# motor.net
KiCad netlist of a schematic drawn in EAGLE
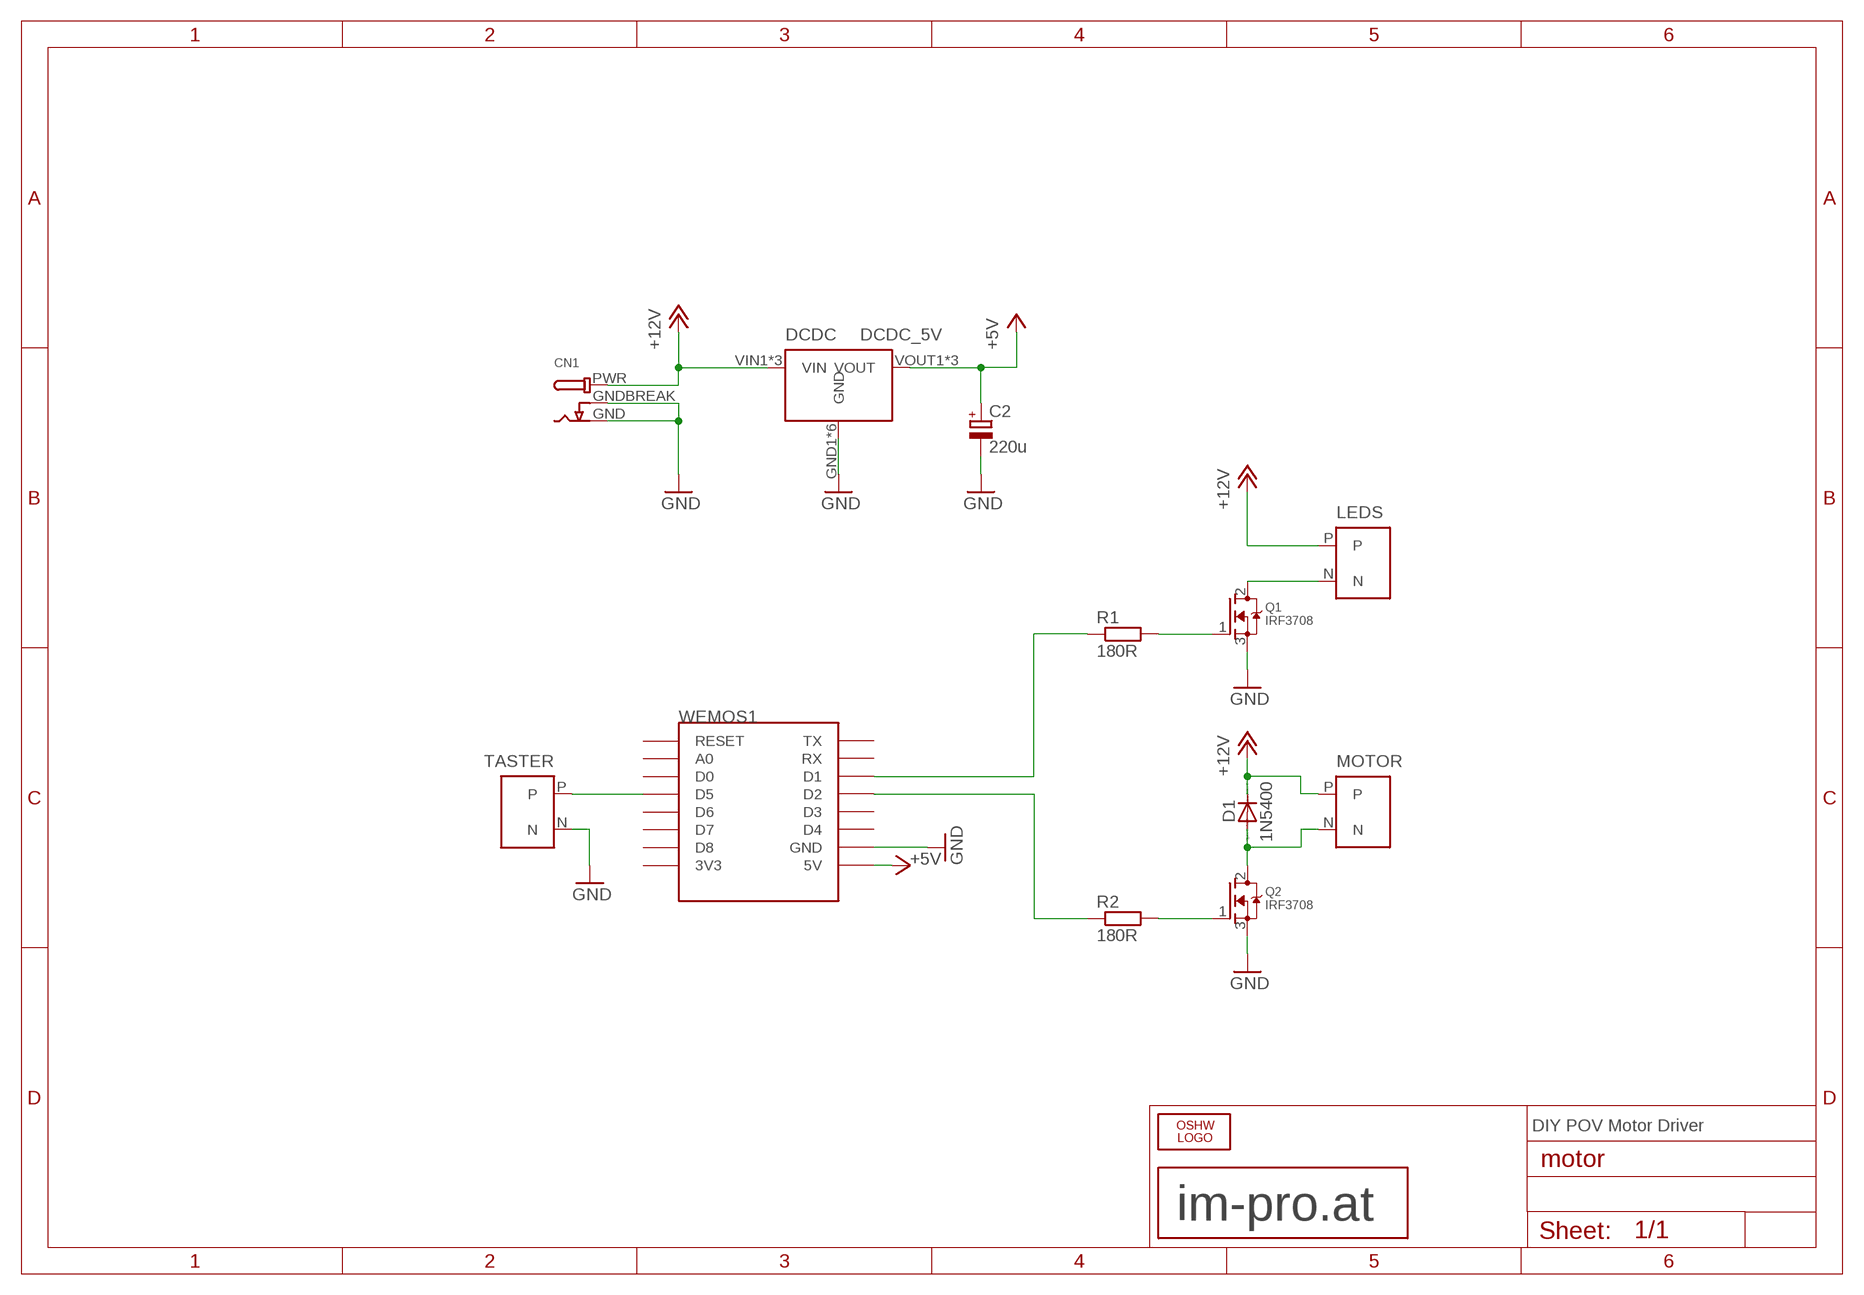
[diagram p0: schematic, sheet 1]

(export (version "E")
  (design (tool "Eeschema 10.0.6"))
  (components
    (comp (ref "C2")
      (value "220u")
      (footprint "eagle-import:E3,5-8")
      (libsource (lib "eagle-import") (part "CPOL-EUE3.5-8"))
    )
    (comp (ref "CN1")
      (value "DCBARRELPTH")
      (footprint "eagle-import:DCJACK_2MM_PTH")
      (libsource (lib "eagle-import") (part "DCBARRELPTH"))
    )
    (comp (ref "D1")
      (value "1N5400")
      (footprint "eagle-import:DO201-15")
      (libsource (lib "eagle-import") (part "1N5400"))
    )
    (comp (ref "DCDC")
      (value "DCDC_5V")
      (footprint "eagle-import:DCDC")
      (libsource (lib "eagle-import") (part "DCDC_5V"))
    )
    (comp (ref "LEDS")
      (value "TX30")
      (footprint "eagle-import:XT30")
      (libsource (lib "eagle-import") (part "TX30"))
    )
    (comp (ref "LOGO1")
      (value "OSHW_LOGO_FILLX0350-NT")
      (footprint "eagle-import:OSHW_FILLX350_NOTEXT")
      (libsource (lib "eagle-import") (part "OSHW_LOGO_FILLX0350-NT"))
    )
    (comp (ref "MOTOR")
      (value "TX30")
      (footprint "eagle-import:XT30")
      (libsource (lib "eagle-import") (part "TX30"))
    )
    (comp (ref "Q1")
      (value "IRF3708")
      (footprint "eagle-import:TO220V")
      (libsource (lib "eagle-import") (part "MOSFET-NGDS_TO220V"))
    )
    (comp (ref "Q2")
      (value "IRF3708")
      (footprint "eagle-import:TO220V")
      (libsource (lib "eagle-import") (part "MOSFET-NGDS_TO220V"))
    )
    (comp (ref "R1")
      (value "180R")
      (footprint "eagle-import:0207_10")
      (libsource (lib "eagle-import") (part "R-EU_0207/10"))
    )
    (comp (ref "R2")
      (value "180R")
      (footprint "eagle-import:0207_10")
      (libsource (lib "eagle-import") (part "R-EU_0207/10"))
    )
    (comp (ref "TASTER")
      (value "TX30")
      (footprint "eagle-import:XT30")
      (libsource (lib "eagle-import") (part "TX30"))
    )
    (comp (ref "U$1")
      (value "LOGO20MM")
      (footprint "eagle-import:LOGO_20MM")
      (libsource (lib "eagle-import") (part "LOGO20MM"))
    )
    (comp (ref "WEMOS1")
      (value "WEMOS-D1-MINI")
      (footprint "eagle-import:WEMOS-D1-MINI")
      (libsource (lib "eagle-import") (part "WEMOS-D1-MINI"))
    )
  )
  (nets
    (net (code "1") (name "+5V") (class "Default")
      (node (ref "C2") (pin "+") (pinfunction "+_+") (pintype "passive"))
      (node (ref "DCDC") (pin "VOUT1") (pinfunction "VOUT_VOUT1") (pintype "power_in"))
      (node (ref "DCDC") (pin "VOUT2") (pinfunction "VOUT_VOUT2") (pintype "power_in"))
      (node (ref "DCDC") (pin "VOUT3") (pinfunction "VOUT_VOUT3") (pintype "power_in"))
      (node (ref "WEMOS1") (pin "5V") (pinfunction "5V_5V") (pintype "bidirectional"))
    )
    (net (code "2") (name "+12V") (class "Default")
      (node (ref "CN1") (pin "PWR") (pinfunction "PWR_PWR") (pintype "power_in"))
      (node (ref "D1") (pin "C") (pinfunction "C_C") (pintype "passive"))
      (node (ref "DCDC") (pin "VIN1") (pinfunction "VIN_VIN1") (pintype "power_in"))
      (node (ref "DCDC") (pin "VIN2") (pinfunction "VIN_VIN2") (pintype "power_in"))
      (node (ref "DCDC") (pin "VIN3") (pinfunction "VIN_VIN3") (pintype "power_in"))
      (node (ref "LEDS") (pin "P") (pinfunction "P_P") (pintype "power_in"))
      (node (ref "MOTOR") (pin "P") (pinfunction "P_P") (pintype "power_in"))
    )
    (net (code "3") (name "GND") (class "Default")
      (node (ref "C2") (pin "-") (pinfunction "-_-") (pintype "passive"))
      (node (ref "CN1") (pin "GND") (pinfunction "GND_GND") (pintype "power_in"))
      (node (ref "CN1") (pin "GNDBREAK") (pinfunction "GNDBREAK_GNDBREAK") (pintype "power_in"))
      (node (ref "DCDC") (pin "GND1") (pinfunction "GND_GND1") (pintype "power_in"))
      (node (ref "DCDC") (pin "GND2") (pinfunction "GND_GND2") (pintype "power_in"))
      (node (ref "DCDC") (pin "GND3") (pinfunction "GND_GND3") (pintype "power_in"))
      (node (ref "DCDC") (pin "GND4") (pinfunction "GND_GND4") (pintype "power_in"))
      (node (ref "DCDC") (pin "GND5") (pinfunction "GND_GND5") (pintype "power_in"))
      (node (ref "DCDC") (pin "GND6") (pinfunction "GND_GND6") (pintype "power_in"))
      (node (ref "Q1") (pin "3") (pinfunction "S_3") (pintype "bidirectional"))
      (node (ref "Q2") (pin "3") (pinfunction "S_3") (pintype "bidirectional"))
      (node (ref "TASTER") (pin "N") (pinfunction "N_N") (pintype "power_in"))
      (node (ref "WEMOS1") (pin "GND") (pinfunction "GND_GND") (pintype "bidirectional"))
    )
    (net (code "4") (name "Net-(Q1-D)") (class "Default")
      (node (ref "LEDS") (pin "N") (pinfunction "N_N") (pintype "power_in"))
      (node (ref "Q1") (pin "2") (pinfunction "D_2") (pintype "bidirectional"))
    )
    (net (code "5") (name "Net-(Q1-G)") (class "Default")
      (node (ref "Q1") (pin "1") (pinfunction "G_1") (pintype "bidirectional"))
      (node (ref "R1") (pin "2") (pinfunction "2_2") (pintype "passive"))
    )
    (net (code "6") (name "Net-(Q2-D)") (class "Default")
      (node (ref "D1") (pin "A") (pinfunction "A_A") (pintype "passive"))
      (node (ref "MOTOR") (pin "N") (pinfunction "N_N") (pintype "power_in"))
      (node (ref "Q2") (pin "2") (pinfunction "D_2") (pintype "bidirectional"))
    )
    (net (code "7") (name "Net-(Q2-G)") (class "Default")
      (node (ref "Q2") (pin "1") (pinfunction "G_1") (pintype "bidirectional"))
      (node (ref "R2") (pin "2") (pinfunction "2_2") (pintype "passive"))
    )
    (net (code "8") (name "Net-(R1-Pad1)") (class "Default")
      (node (ref "R1") (pin "1") (pinfunction "1_1") (pintype "passive"))
      (node (ref "WEMOS1") (pin "D1") (pinfunction "D1_D1") (pintype "bidirectional"))
    )
    (net (code "9") (name "Net-(R2-Pad1)") (class "Default")
      (node (ref "R2") (pin "1") (pinfunction "1_1") (pintype "passive"))
      (node (ref "WEMOS1") (pin "D2") (pinfunction "D2_D2") (pintype "bidirectional"))
    )
    (net (code "10") (name "Net-(TASTER-PadP)") (class "Default")
      (node (ref "TASTER") (pin "P") (pinfunction "P_P") (pintype "power_in"))
      (node (ref "WEMOS1") (pin "D5") (pinfunction "D5_D5") (pintype "bidirectional"))
    )
    (net (code "11") (name "unconnected-(WEMOS1-Pad3V3)") (class "Default")
      (node (ref "WEMOS1") (pin "3V3") (pinfunction "3V3_3V3") (pintype "bidirectional"))
    )
    (net (code "12") (name "unconnected-(WEMOS1-PadA0)") (class "Default")
      (node (ref "WEMOS1") (pin "A0") (pinfunction "A0_A0") (pintype "bidirectional"))
    )
    (net (code "13") (name "unconnected-(WEMOS1-PadD0)") (class "Default")
      (node (ref "WEMOS1") (pin "D0") (pinfunction "D0_D0") (pintype "bidirectional"))
    )
    (net (code "14") (name "unconnected-(WEMOS1-PadD3)") (class "Default")
      (node (ref "WEMOS1") (pin "D3") (pinfunction "D3_D3") (pintype "bidirectional"))
    )
    (net (code "15") (name "unconnected-(WEMOS1-PadD4)") (class "Default")
      (node (ref "WEMOS1") (pin "D4") (pinfunction "D4_D4") (pintype "bidirectional"))
    )
    (net (code "16") (name "unconnected-(WEMOS1-PadD6)") (class "Default")
      (node (ref "WEMOS1") (pin "D6") (pinfunction "D6_D6") (pintype "bidirectional"))
    )
    (net (code "17") (name "unconnected-(WEMOS1-PadD7)") (class "Default")
      (node (ref "WEMOS1") (pin "D7") (pinfunction "D7_D7") (pintype "bidirectional"))
    )
    (net (code "18") (name "unconnected-(WEMOS1-PadD8)") (class "Default")
      (node (ref "WEMOS1") (pin "D8") (pinfunction "D8_D8") (pintype "bidirectional"))
    )
    (net (code "19") (name "unconnected-(WEMOS1-PadRESET)") (class "Default")
      (node (ref "WEMOS1") (pin "RESET") (pinfunction "RESET_RESET") (pintype "bidirectional"))
    )
    (net (code "20") (name "unconnected-(WEMOS1-PadRX)") (class "Default")
      (node (ref "WEMOS1") (pin "RX") (pinfunction "RX_RX") (pintype "bidirectional"))
    )
    (net (code "21") (name "unconnected-(WEMOS1-PadTX)") (class "Default")
      (node (ref "WEMOS1") (pin "TX") (pinfunction "TX_TX") (pintype "bidirectional"))
    )
  )
)
